# schematic.net
KiCad netlist of a schematic drawn in EAGLE
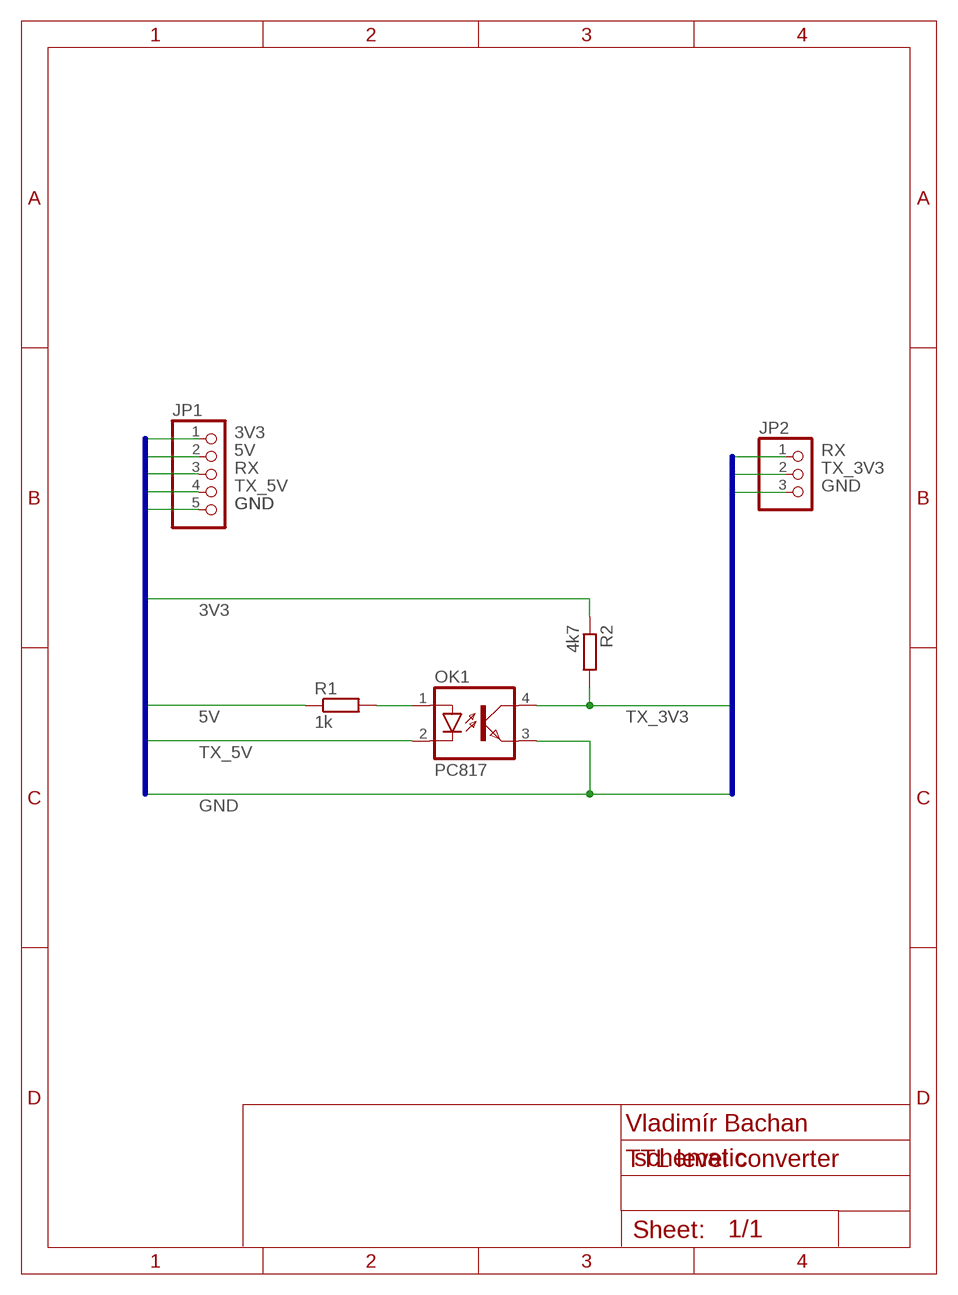
[diagram p0: schematic, sheet 1]

(export (version "E")
  (design (tool "Eeschema 10.0.6"))
  (components
    (comp (ref "JP1")
      (value "PINHD-1X5")
      (footprint "eagle-import:1X05")
      (libsource (lib "eagle-import") (part "PINHD-1X5"))
    )
    (comp (ref "JP2")
      (value "PINHD-1X3")
      (footprint "eagle-import:1X03")
      (libsource (lib "eagle-import") (part "PINHD-1X3"))
    )
    (comp (ref "OK1")
      (value "PC817")
      (footprint "eagle-import:DIL04")
      (fields (field (name "MPN") "PC817X4J000F"))
      (libsource (lib "eagle-import") (part "PC817"))
    )
    (comp (ref "R1")
      (value "1k")
      (footprint "eagle-import:0207_10")
      (libsource (lib "eagle-import") (part "R-EU_0207/10"))
    )
    (comp (ref "R2")
      (value "4k7")
      (footprint "eagle-import:0207_10")
      (libsource (lib "eagle-import") (part "R-EU_0207/10"))
    )
  )
  (nets
    (net (code "1") (name "/3V3") (class "Default")
      (node (ref "JP1") (pin "1") (pinfunction "1_1") (pintype "passive"))
      (node (ref "R2") (pin "1") (pinfunction "1_1") (pintype "passive"))
    )
    (net (code "2") (name "/5V") (class "Default")
      (node (ref "JP1") (pin "2") (pinfunction "2_2") (pintype "passive"))
      (node (ref "R1") (pin "1") (pinfunction "1_1") (pintype "passive"))
    )
    (net (code "3") (name "/GND") (class "Default")
      (node (ref "JP1") (pin "5") (pinfunction "5_5") (pintype "passive"))
      (node (ref "JP2") (pin "3") (pinfunction "3_3") (pintype "passive"))
      (node (ref "OK1") (pin "3") (pinfunction "EMIT_3") (pintype "passive"))
    )
    (net (code "4") (name "/RX") (class "Default")
      (node (ref "JP1") (pin "3") (pinfunction "3_3") (pintype "passive"))
      (node (ref "JP2") (pin "1") (pinfunction "1_1") (pintype "passive"))
    )
    (net (code "5") (name "/TX_3V3") (class "Default")
      (node (ref "JP2") (pin "2") (pinfunction "2_2") (pintype "passive"))
      (node (ref "OK1") (pin "4") (pinfunction "COL_4") (pintype "passive"))
      (node (ref "R2") (pin "2") (pinfunction "2_2") (pintype "passive"))
    )
    (net (code "6") (name "/TX_5V") (class "Default")
      (node (ref "JP1") (pin "4") (pinfunction "4_4") (pintype "passive"))
      (node (ref "OK1") (pin "2") (pinfunction "C_2") (pintype "passive"))
    )
    (net (code "7") (name "Net-(OK1-A)") (class "Default")
      (node (ref "OK1") (pin "1") (pinfunction "A_1") (pintype "passive"))
      (node (ref "R1") (pin "2") (pinfunction "2_2") (pintype "passive"))
    )
  )
)
